# Minimal_carrier_board_for_CM4_rev_C.net
KiCad netlist of a schematic drawn in EAGLE
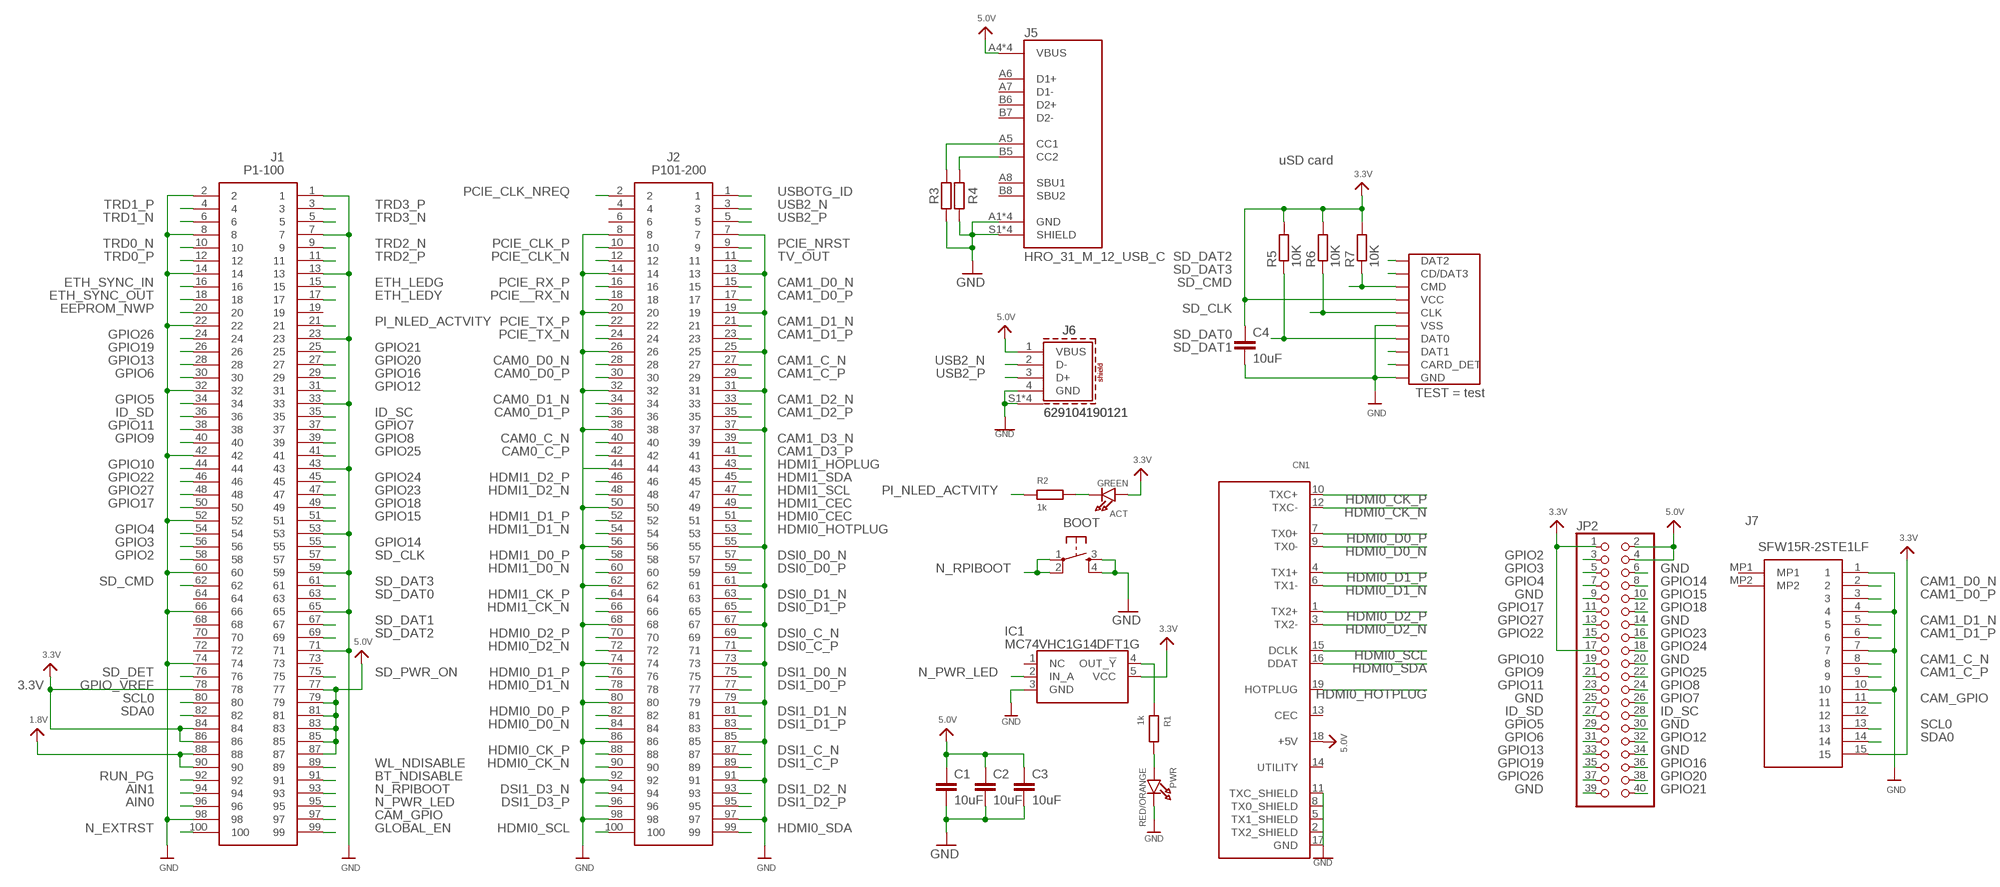
[diagram p0: schematic, sheet 1]

(export (version "E")
  (design (tool "Eeschema 10.0.6"))
  (components
    (comp (ref "ACT")
      (value "GREEN")
      (footprint "eagle-import:CHIPLED_0805_NOOUTLINE")
      (libsource (lib "eagle-import") (part "LED0805_NOOUTLINE"))
    )
    (comp (ref "BOOT")
      (value "TACTILE_SWITCHE_5X5_MICRO_")
      (footprint "eagle-import:TACTILE_SWITCH_5X5_MICRO")
      (libsource (lib "eagle-import") (part "TACTILE_SWITCHE_5X5_MICRO_"))
    )
    (comp (ref "C1")
      (value "10uF")
      (footprint "eagle-import:C0805")
      (libsource (lib "eagle-import") (part "C-EUC0805"))
    )
    (comp (ref "C2")
      (value "10uF")
      (footprint "eagle-import:C0805")
      (libsource (lib "eagle-import") (part "C-EUC0805"))
    )
    (comp (ref "C3")
      (value "10uF")
      (footprint "eagle-import:C0805")
      (libsource (lib "eagle-import") (part "C-EUC0805"))
    )
    (comp (ref "C4")
      (value "10uF")
      (footprint "eagle-import:C0805")
      (libsource (lib "eagle-import") (part "C-EUC0805"))
    )
    (comp (ref "CN1")
      (value "HDMI_MOLEX_47151-0001")
      (footprint "eagle-import:HDMI_MOLEX_47151-0001")
      (libsource (lib "eagle-import") (part "HDMI_MOLEX_47151-0001"))
    )
    (comp (ref "IC1")
      (value "MC74VHC1G14DFT1G")
      (footprint "eagle-import:SOT65P210X110-5N")
      (fields (field (name "MOUSER_PART_NUMBER") "863-MC74VHC1G14DFT1G"))
      (libsource (lib "eagle-import") (part "MC74VHC1G14DFT1G"))
    )
    (comp (ref "J1")
      (value "P1-100")
      (footprint "eagle-import:DF40C100DS04V51")
      (fields
        (field (name "MANUFACTURER_PART_NUMBER") "DF40C-100DS-0.4V(51)")
        (field (name "MOUSER_PART_NUMBER") "798-DF40C100DS0.4V51")
      )
      (libsource (lib "eagle-import") (part "DF40C-100DS-0.4V_51_"))
    )
    (comp (ref "J2")
      (value "P101-200")
      (footprint "eagle-import:DF40C100DS04V51")
      (fields
        (field (name "MANUFACTURER_PART_NUMBER") "DF40C-100DS-0.4V(51)")
        (field (name "MOUSER_PART_NUMBER") "798-DF40C100DS0.4V51")
      )
      (libsource (lib "eagle-import") (part "DF40C-100DS-0.4V_51_"))
    )
    (comp (ref "J5")
      (value "HRO_31_M_12_USB_C")
      (footprint "eagle-import:HRO_31_M_12_USB_C")
      (libsource (lib "eagle-import") (part "HRO_31_M_12_USB_C"))
    )
    (comp (ref "J6")
      (value "629104190121")
      (footprint "eagle-import:629104190121")
      (libsource (lib "eagle-import") (part "629104190121"))
    )
    (comp (ref "J7")
      (value "SFW15R-2STE1LF")
      (footprint "eagle-import:SFW15R2STE1LF")
      (fields (field (name "MOUSER_PART_NUMBER") "649-SFW15R-2STE1LF"))
      (libsource (lib "eagle-import") (part "SFW15R-2STE1LF"))
    )
    (comp (ref "JP2")
      (value "PINHD-2X20")
      (footprint "eagle-import:2X20")
      (libsource (lib "eagle-import") (part "PINHD-2X20"))
    )
    (comp (ref "PWR")
      (value "RED/ORANGE")
      (footprint "eagle-import:CHIPLED_0805_NOOUTLINE")
      (libsource (lib "eagle-import") (part "LED0805_NOOUTLINE"))
    )
    (comp (ref "R1")
      (value "1k")
      (footprint "eagle-import:R0805")
      (libsource (lib "eagle-import") (part "R-EU_R0805"))
    )
    (comp (ref "R2")
      (value "1k")
      (footprint "eagle-import:R0805")
      (libsource (lib "eagle-import") (part "R-EU_R0805"))
    )
    (comp (ref "R3")
      (value "5.1k")
      (footprint "eagle-import:R0805")
      (libsource (lib "eagle-import") (part "R-EU_R0805"))
    )
    (comp (ref "R4")
      (value "5.1k")
      (footprint "eagle-import:R0805")
      (libsource (lib "eagle-import") (part "R-EU_R0805"))
    )
    (comp (ref "R5")
      (value "10K")
      (footprint "eagle-import:R0805")
      (libsource (lib "eagle-import") (part "R-EU_R0805"))
    )
    (comp (ref "R6")
      (value "10K")
      (footprint "eagle-import:R0805")
      (libsource (lib "eagle-import") (part "R-EU_R0805"))
    )
    (comp (ref "R7")
      (value "10K")
      (footprint "eagle-import:R0805")
      (libsource (lib "eagle-import") (part "R-EU_R0805"))
    )
    (comp (ref "SD_CARD")
      (value "MICRO_SD_CARD_")
      (footprint "eagle-import:TFP09-2--12B")
      (fields (field (name "TEST") "test"))
      (libsource (lib "eagle-import") (part "MICRO_SD_CARD_"))
    )
  )
  (nets
    (net (code "1") (name "/AIN0") (class "Default")
      (node (ref "J1") (pin "96") (pinfunction "96_96") (pintype "bidirectional"))
    )
    (net (code "2") (name "/AIN1") (class "Default")
      (node (ref "J1") (pin "94") (pinfunction "94_94") (pintype "bidirectional"))
    )
    (net (code "3") (name "/BT_NDISABLE") (class "Default")
      (node (ref "J1") (pin "91") (pinfunction "91_91") (pintype "bidirectional"))
    )
    (net (code "4") (name "/CAM0_C_N") (class "Default")
      (node (ref "J2") (pin "40") (pinfunction "40_40") (pintype "bidirectional"))
    )
    (net (code "5") (name "/CAM0_C_P") (class "Default")
      (node (ref "J2") (pin "42") (pinfunction "42_42") (pintype "bidirectional"))
    )
    (net (code "6") (name "/CAM0_D0_N") (class "Default")
      (node (ref "J2") (pin "28") (pinfunction "28_28") (pintype "bidirectional"))
    )
    (net (code "7") (name "/CAM0_D0_P") (class "Default")
      (node (ref "J2") (pin "30") (pinfunction "30_30") (pintype "bidirectional"))
    )
    (net (code "8") (name "/CAM0_D1_N") (class "Default")
      (node (ref "J2") (pin "34") (pinfunction "34_34") (pintype "bidirectional"))
    )
    (net (code "9") (name "/CAM0_D1_P") (class "Default")
      (node (ref "J2") (pin "36") (pinfunction "36_36") (pintype "bidirectional"))
    )
    (net (code "10") (name "/CAM1_C_N") (class "Default")
      (node (ref "J2") (pin "27") (pinfunction "27_27") (pintype "bidirectional"))
      (node (ref "J7") (pin "8") (pinfunction "8_8") (pintype "bidirectional"))
    )
    (net (code "11") (name "/CAM1_C_P") (class "Default")
      (node (ref "J2") (pin "29") (pinfunction "29_29") (pintype "bidirectional"))
      (node (ref "J7") (pin "9") (pinfunction "9_9") (pintype "bidirectional"))
    )
    (net (code "12") (name "/CAM1_D0_N") (class "Default")
      (node (ref "J2") (pin "15") (pinfunction "15_15") (pintype "bidirectional"))
      (node (ref "J7") (pin "2") (pinfunction "2_2") (pintype "bidirectional"))
    )
    (net (code "13") (name "/CAM1_D0_P") (class "Default")
      (node (ref "J2") (pin "17") (pinfunction "17_17") (pintype "bidirectional"))
      (node (ref "J7") (pin "3") (pinfunction "3_3") (pintype "bidirectional"))
    )
    (net (code "14") (name "/CAM1_D1_N") (class "Default")
      (node (ref "J2") (pin "21") (pinfunction "21_21") (pintype "bidirectional"))
      (node (ref "J7") (pin "5") (pinfunction "5_5") (pintype "bidirectional"))
    )
    (net (code "15") (name "/CAM1_D1_P") (class "Default")
      (node (ref "J2") (pin "23") (pinfunction "23_23") (pintype "bidirectional"))
      (node (ref "J7") (pin "6") (pinfunction "6_6") (pintype "bidirectional"))
    )
    (net (code "16") (name "/CAM1_D2_N") (class "Default")
      (node (ref "J2") (pin "33") (pinfunction "33_33") (pintype "bidirectional"))
    )
    (net (code "17") (name "/CAM1_D2_P") (class "Default")
      (node (ref "J2") (pin "35") (pinfunction "35_35") (pintype "bidirectional"))
    )
    (net (code "18") (name "/CAM1_D3_N") (class "Default")
      (node (ref "J2") (pin "39") (pinfunction "39_39") (pintype "bidirectional"))
    )
    (net (code "19") (name "/CAM1_D3_P") (class "Default")
      (node (ref "J2") (pin "41") (pinfunction "41_41") (pintype "bidirectional"))
    )
    (net (code "20") (name "/CAM_GPIO") (class "Default")
      (node (ref "J1") (pin "97") (pinfunction "97_97") (pintype "bidirectional"))
      (node (ref "J7") (pin "11") (pinfunction "11_11") (pintype "bidirectional"))
    )
    (net (code "21") (name "/DSI0_C_N") (class "Default")
      (node (ref "J2") (pin "69") (pinfunction "69_69") (pintype "bidirectional"))
    )
    (net (code "22") (name "/DSI0_C_P") (class "Default")
      (node (ref "J2") (pin "71") (pinfunction "71_71") (pintype "bidirectional"))
    )
    (net (code "23") (name "/DSI0_D0_N") (class "Default")
      (node (ref "J2") (pin "57") (pinfunction "57_57") (pintype "bidirectional"))
    )
    (net (code "24") (name "/DSI0_D0_P") (class "Default")
      (node (ref "J2") (pin "59") (pinfunction "59_59") (pintype "bidirectional"))
    )
    (net (code "25") (name "/DSI0_D1_N") (class "Default")
      (node (ref "J2") (pin "63") (pinfunction "63_63") (pintype "bidirectional"))
    )
    (net (code "26") (name "/DSI0_D1_P") (class "Default")
      (node (ref "J2") (pin "65") (pinfunction "65_65") (pintype "bidirectional"))
    )
    (net (code "27") (name "/DSI1_C_N") (class "Default")
      (node (ref "J2") (pin "87") (pinfunction "87_87") (pintype "bidirectional"))
    )
    (net (code "28") (name "/DSI1_C_P") (class "Default")
      (node (ref "J2") (pin "89") (pinfunction "89_89") (pintype "bidirectional"))
    )
    (net (code "29") (name "/DSI1_D0_N") (class "Default")
      (node (ref "J2") (pin "75") (pinfunction "75_75") (pintype "bidirectional"))
    )
    (net (code "30") (name "/DSI1_D0_P") (class "Default")
      (node (ref "J2") (pin "77") (pinfunction "77_77") (pintype "bidirectional"))
    )
    (net (code "31") (name "/DSI1_D1_N") (class "Default")
      (node (ref "J2") (pin "81") (pinfunction "81_81") (pintype "bidirectional"))
    )
    (net (code "32") (name "/DSI1_D1_P") (class "Default")
      (node (ref "J2") (pin "83") (pinfunction "83_83") (pintype "bidirectional"))
    )
    (net (code "33") (name "/DSI1_D2_N") (class "Default")
      (node (ref "J2") (pin "93") (pinfunction "93_93") (pintype "bidirectional"))
    )
    (net (code "34") (name "/DSI1_D2_P") (class "Default")
      (node (ref "J2") (pin "95") (pinfunction "95_95") (pintype "bidirectional"))
    )
    (net (code "35") (name "/DSI1_D3_N") (class "Default")
      (node (ref "J2") (pin "94") (pinfunction "94_94") (pintype "bidirectional"))
    )
    (net (code "36") (name "/DSI1_D3_P") (class "Default")
      (node (ref "J2") (pin "96") (pinfunction "96_96") (pintype "bidirectional"))
    )
    (net (code "37") (name "/EEPROM_NWP") (class "Default")
      (node (ref "J1") (pin "20") (pinfunction "20_20") (pintype "bidirectional"))
    )
    (net (code "38") (name "/ETH_LEDG") (class "Default")
      (node (ref "J1") (pin "15") (pinfunction "15_15") (pintype "bidirectional"))
    )
    (net (code "39") (name "/ETH_LEDY") (class "Default")
      (node (ref "J1") (pin "17") (pinfunction "17_17") (pintype "bidirectional"))
    )
    (net (code "40") (name "/ETH_SYNC_IN") (class "Default")
      (node (ref "J1") (pin "16") (pinfunction "16_16") (pintype "bidirectional"))
    )
    (net (code "41") (name "/ETH_SYNC_OUT") (class "Default")
      (node (ref "J1") (pin "18") (pinfunction "18_18") (pintype "bidirectional"))
    )
    (net (code "42") (name "/GLOBAL_EN") (class "Default")
      (node (ref "J1") (pin "99") (pinfunction "99_99") (pintype "bidirectional"))
    )
    (net (code "43") (name "/GPIO2") (class "Default")
      (node (ref "J1") (pin "58") (pinfunction "58_58") (pintype "bidirectional"))
      (node (ref "JP2") (pin "3") (pinfunction "3_3") (pintype "passive"))
    )
    (net (code "44") (name "/GPIO3") (class "Default")
      (node (ref "J1") (pin "56") (pinfunction "56_56") (pintype "bidirectional"))
      (node (ref "JP2") (pin "5") (pinfunction "5_5") (pintype "passive"))
    )
    (net (code "45") (name "/GPIO4") (class "Default")
      (node (ref "J1") (pin "54") (pinfunction "54_54") (pintype "bidirectional"))
      (node (ref "JP2") (pin "7") (pinfunction "7_7") (pintype "passive"))
    )
    (net (code "46") (name "/GPIO5") (class "Default")
      (node (ref "J1") (pin "34") (pinfunction "34_34") (pintype "bidirectional"))
      (node (ref "JP2") (pin "29") (pinfunction "29_29") (pintype "passive"))
    )
    (net (code "47") (name "/GPIO6") (class "Default")
      (node (ref "J1") (pin "30") (pinfunction "30_30") (pintype "bidirectional"))
      (node (ref "JP2") (pin "31") (pinfunction "31_31") (pintype "passive"))
    )
    (net (code "48") (name "/GPIO7") (class "Default")
      (node (ref "J1") (pin "37") (pinfunction "37_37") (pintype "bidirectional"))
      (node (ref "JP2") (pin "26") (pinfunction "26_26") (pintype "passive"))
    )
    (net (code "49") (name "/GPIO8") (class "Default")
      (node (ref "J1") (pin "39") (pinfunction "39_39") (pintype "bidirectional"))
      (node (ref "JP2") (pin "24") (pinfunction "24_24") (pintype "passive"))
    )
    (net (code "50") (name "/GPIO9") (class "Default")
      (node (ref "J1") (pin "40") (pinfunction "40_40") (pintype "bidirectional"))
      (node (ref "JP2") (pin "21") (pinfunction "21_21") (pintype "passive"))
    )
    (net (code "51") (name "/GPIO10") (class "Default")
      (node (ref "J1") (pin "44") (pinfunction "44_44") (pintype "bidirectional"))
      (node (ref "JP2") (pin "19") (pinfunction "19_19") (pintype "passive"))
    )
    (net (code "52") (name "/GPIO11") (class "Default")
      (node (ref "J1") (pin "38") (pinfunction "38_38") (pintype "bidirectional"))
      (node (ref "JP2") (pin "23") (pinfunction "23_23") (pintype "passive"))
    )
    (net (code "53") (name "/GPIO12") (class "Default")
      (node (ref "J1") (pin "31") (pinfunction "31_31") (pintype "bidirectional"))
      (node (ref "JP2") (pin "32") (pinfunction "32_32") (pintype "passive"))
    )
    (net (code "54") (name "/GPIO13") (class "Default")
      (node (ref "J1") (pin "28") (pinfunction "28_28") (pintype "bidirectional"))
      (node (ref "JP2") (pin "33") (pinfunction "33_33") (pintype "passive"))
    )
    (net (code "55") (name "/GPIO14") (class "Default")
      (node (ref "J1") (pin "55") (pinfunction "55_55") (pintype "bidirectional"))
      (node (ref "JP2") (pin "8") (pinfunction "8_8") (pintype "passive"))
    )
    (net (code "56") (name "/GPIO15") (class "Default")
      (node (ref "J1") (pin "51") (pinfunction "51_51") (pintype "bidirectional"))
      (node (ref "JP2") (pin "10") (pinfunction "10_10") (pintype "passive"))
    )
    (net (code "57") (name "/GPIO16") (class "Default")
      (node (ref "J1") (pin "29") (pinfunction "29_29") (pintype "bidirectional"))
      (node (ref "JP2") (pin "36") (pinfunction "36_36") (pintype "passive"))
    )
    (net (code "58") (name "/GPIO17") (class "Default")
      (node (ref "J1") (pin "50") (pinfunction "50_50") (pintype "bidirectional"))
      (node (ref "JP2") (pin "11") (pinfunction "11_11") (pintype "passive"))
    )
    (net (code "59") (name "/GPIO18") (class "Default")
      (node (ref "J1") (pin "49") (pinfunction "49_49") (pintype "bidirectional"))
      (node (ref "JP2") (pin "12") (pinfunction "12_12") (pintype "passive"))
    )
    (net (code "60") (name "/GPIO19") (class "Default")
      (node (ref "J1") (pin "26") (pinfunction "26_26") (pintype "bidirectional"))
      (node (ref "JP2") (pin "35") (pinfunction "35_35") (pintype "passive"))
    )
    (net (code "61") (name "/GPIO20") (class "Default")
      (node (ref "J1") (pin "27") (pinfunction "27_27") (pintype "bidirectional"))
      (node (ref "JP2") (pin "38") (pinfunction "38_38") (pintype "passive"))
    )
    (net (code "62") (name "/GPIO21") (class "Default")
      (node (ref "J1") (pin "25") (pinfunction "25_25") (pintype "bidirectional"))
      (node (ref "JP2") (pin "40") (pinfunction "40_40") (pintype "passive"))
    )
    (net (code "63") (name "/GPIO22") (class "Default")
      (node (ref "J1") (pin "46") (pinfunction "46_46") (pintype "bidirectional"))
      (node (ref "JP2") (pin "15") (pinfunction "15_15") (pintype "passive"))
    )
    (net (code "64") (name "/GPIO23") (class "Default")
      (node (ref "J1") (pin "47") (pinfunction "47_47") (pintype "bidirectional"))
      (node (ref "JP2") (pin "16") (pinfunction "16_16") (pintype "passive"))
    )
    (net (code "65") (name "/GPIO24") (class "Default")
      (node (ref "J1") (pin "45") (pinfunction "45_45") (pintype "bidirectional"))
      (node (ref "JP2") (pin "18") (pinfunction "18_18") (pintype "passive"))
    )
    (net (code "66") (name "/GPIO25") (class "Default")
      (node (ref "J1") (pin "41") (pinfunction "41_41") (pintype "bidirectional"))
      (node (ref "JP2") (pin "22") (pinfunction "22_22") (pintype "passive"))
    )
    (net (code "67") (name "/GPIO26") (class "Default")
      (node (ref "J1") (pin "24") (pinfunction "24_24") (pintype "bidirectional"))
      (node (ref "JP2") (pin "37") (pinfunction "37_37") (pintype "passive"))
    )
    (net (code "68") (name "/GPIO27") (class "Default")
      (node (ref "J1") (pin "48") (pinfunction "48_48") (pintype "bidirectional"))
      (node (ref "JP2") (pin "13") (pinfunction "13_13") (pintype "passive"))
    )
    (net (code "69") (name "/HDMI0_CEC") (class "Default")
      (node (ref "J2") (pin "51") (pinfunction "51_51") (pintype "bidirectional"))
    )
    (net (code "70") (name "/HDMI0_CK_N") (class "Default")
      (node (ref "CN1") (pin "12") (pinfunction "TXC-_12") (pintype "bidirectional"))
      (node (ref "J2") (pin "90") (pinfunction "90_90") (pintype "bidirectional"))
    )
    (net (code "71") (name "/HDMI0_CK_P") (class "Default")
      (node (ref "CN1") (pin "10") (pinfunction "TXC+_10") (pintype "bidirectional"))
      (node (ref "J2") (pin "88") (pinfunction "88_88") (pintype "bidirectional"))
    )
    (net (code "72") (name "/HDMI0_D0_N") (class "Default")
      (node (ref "CN1") (pin "9") (pinfunction "TX0-_9") (pintype "bidirectional"))
      (node (ref "J2") (pin "84") (pinfunction "84_84") (pintype "bidirectional"))
    )
    (net (code "73") (name "/HDMI0_D0_P") (class "Default")
      (node (ref "CN1") (pin "7") (pinfunction "TX0+_7") (pintype "bidirectional"))
      (node (ref "J2") (pin "82") (pinfunction "82_82") (pintype "bidirectional"))
    )
    (net (code "74") (name "/HDMI0_D1_N") (class "Default")
      (node (ref "CN1") (pin "6") (pinfunction "TX1-_6") (pintype "bidirectional"))
      (node (ref "J2") (pin "78") (pinfunction "78_78") (pintype "bidirectional"))
    )
    (net (code "75") (name "/HDMI0_D1_P") (class "Default")
      (node (ref "CN1") (pin "4") (pinfunction "TX1+_4") (pintype "bidirectional"))
      (node (ref "J2") (pin "76") (pinfunction "76_76") (pintype "bidirectional"))
    )
    (net (code "76") (name "/HDMI0_D2_N") (class "Default")
      (node (ref "CN1") (pin "3") (pinfunction "TX2-_3") (pintype "bidirectional"))
      (node (ref "J2") (pin "72") (pinfunction "72_72") (pintype "bidirectional"))
    )
    (net (code "77") (name "/HDMI0_D2_P") (class "Default")
      (node (ref "CN1") (pin "1") (pinfunction "TX2+_1") (pintype "bidirectional"))
      (node (ref "J2") (pin "70") (pinfunction "70_70") (pintype "bidirectional"))
    )
    (net (code "78") (name "/HDMI0_HOTPLUG") (class "Default")
      (node (ref "CN1") (pin "19") (pinfunction "HOTPLUG_19") (pintype "bidirectional"))
      (node (ref "J2") (pin "53") (pinfunction "53_53") (pintype "bidirectional"))
    )
    (net (code "79") (name "/HDMI0_SCL") (class "Default")
      (node (ref "CN1") (pin "15") (pinfunction "DCLK_15") (pintype "bidirectional"))
      (node (ref "J2") (pin "100") (pinfunction "100_100") (pintype "bidirectional"))
    )
    (net (code "80") (name "/HDMI0_SDA") (class "Default")
      (node (ref "CN1") (pin "16") (pinfunction "DDAT_16") (pintype "bidirectional"))
      (node (ref "J2") (pin "99") (pinfunction "99_99") (pintype "bidirectional"))
    )
    (net (code "81") (name "/HDMI1_CEC") (class "Default")
      (node (ref "J2") (pin "49") (pinfunction "49_49") (pintype "bidirectional"))
    )
    (net (code "82") (name "/HDMI1_CK_N") (class "Default")
      (node (ref "J2") (pin "66") (pinfunction "66_66") (pintype "bidirectional"))
    )
    (net (code "83") (name "/HDMI1_CK_P") (class "Default")
      (node (ref "J2") (pin "64") (pinfunction "64_64") (pintype "bidirectional"))
    )
    (net (code "84") (name "/HDMI1_D0_N") (class "Default")
      (node (ref "J2") (pin "60") (pinfunction "60_60") (pintype "bidirectional"))
    )
    (net (code "85") (name "/HDMI1_D0_P") (class "Default")
      (node (ref "J2") (pin "58") (pinfunction "58_58") (pintype "bidirectional"))
    )
    (net (code "86") (name "/HDMI1_D1_N") (class "Default")
      (node (ref "J2") (pin "54") (pinfunction "54_54") (pintype "bidirectional"))
    )
    (net (code "87") (name "/HDMI1_D1_P") (class "Default")
      (node (ref "J2") (pin "52") (pinfunction "52_52") (pintype "bidirectional"))
    )
    (net (code "88") (name "/HDMI1_D2_N") (class "Default")
      (node (ref "J2") (pin "48") (pinfunction "48_48") (pintype "bidirectional"))
    )
    (net (code "89") (name "/HDMI1_D2_P") (class "Default")
      (node (ref "J2") (pin "46") (pinfunction "46_46") (pintype "bidirectional"))
    )
    (net (code "90") (name "/HDMI1_HOPLUG") (class "Default")
      (node (ref "J2") (pin "43") (pinfunction "43_43") (pintype "bidirectional"))
    )
    (net (code "91") (name "/HDMI1_SCL") (class "Default")
      (node (ref "J2") (pin "47") (pinfunction "47_47") (pintype "bidirectional"))
    )
    (net (code "92") (name "/HDMI1_SDA") (class "Default")
      (node (ref "J2") (pin "45") (pinfunction "45_45") (pintype "bidirectional"))
    )
    (net (code "93") (name "/ID_SC") (class "Default")
      (node (ref "J1") (pin "35") (pinfunction "35_35") (pintype "bidirectional"))
      (node (ref "JP2") (pin "28") (pinfunction "28_28") (pintype "passive"))
    )
    (net (code "94") (name "/ID_SD") (class "Default")
      (node (ref "J1") (pin "36") (pinfunction "36_36") (pintype "bidirectional"))
      (node (ref "JP2") (pin "27") (pinfunction "27_27") (pintype "passive"))
    )
    (net (code "95") (name "/N_EXTRST") (class "Default")
      (node (ref "J1") (pin "100") (pinfunction "100_100") (pintype "bidirectional"))
    )
    (net (code "96") (name "/N_PWR_LED") (class "Default")
      (node (ref "IC1") (pin "2") (pinfunction "IN_A_2") (pintype "input"))
      (node (ref "J1") (pin "95") (pinfunction "95_95") (pintype "bidirectional"))
    )
    (net (code "97") (name "/N_RPIBOOT") (class "Default")
      (node (ref "BOOT") (pin "1") (pinfunction "1_1") (pintype "passive"))
      (node (ref "BOOT") (pin "2") (pinfunction "2_2") (pintype "passive"))
      (node (ref "J1") (pin "93") (pinfunction "93_93") (pintype "bidirectional"))
    )
    (net (code "98") (name "/PCIE_CLK_N") (class "Default")
      (node (ref "J2") (pin "12") (pinfunction "12_12") (pintype "bidirectional"))
    )
    (net (code "99") (name "/PCIE_CLK_NREQ") (class "Default")
      (node (ref "J2") (pin "2") (pinfunction "2_2") (pintype "bidirectional"))
    )
    (net (code "100") (name "/PCIE_CLK_P") (class "Default")
      (node (ref "J2") (pin "10") (pinfunction "10_10") (pintype "bidirectional"))
    )
    (net (code "101") (name "/PCIE_NRST") (class "Default")
      (node (ref "J2") (pin "9") (pinfunction "9_9") (pintype "bidirectional"))
    )
    (net (code "102") (name "/PCIE_RX_P") (class "Default")
      (node (ref "J2") (pin "16") (pinfunction "16_16") (pintype "bidirectional"))
    )
    (net (code "103") (name "/PCIE_TX_N") (class "Default")
      (node (ref "J2") (pin "24") (pinfunction "24_24") (pintype "bidirectional"))
    )
    (net (code "104") (name "/PCIE_TX_P") (class "Default")
      (node (ref "J2") (pin "22") (pinfunction "22_22") (pintype "bidirectional"))
    )
    (net (code "105") (name "/PCIE__RX_N") (class "Default")
      (node (ref "J2") (pin "18") (pinfunction "18_18") (pintype "bidirectional"))
    )
    (net (code "106") (name "/PI_NLED_ACTVITY") (class "Default")
      (node (ref "J1") (pin "21") (pinfunction "21_21") (pintype "bidirectional"))
      (node (ref "R2") (pin "1") (pinfunction "1_1") (pintype "passive"))
    )
    (net (code "107") (name "/RUN_PG") (class "Default")
      (node (ref "J1") (pin "92") (pinfunction "92_92") (pintype "bidirectional"))
    )
    (net (code "108") (name "/SCL0") (class "Default")
      (node (ref "J1") (pin "80") (pinfunction "80_80") (pintype "bidirectional"))
      (node (ref "J7") (pin "13") (pinfunction "13_13") (pintype "bidirectional"))
    )
    (net (code "109") (name "/SDA0") (class "Default")
      (node (ref "J1") (pin "82") (pinfunction "82_82") (pintype "bidirectional"))
      (node (ref "J7") (pin "14") (pinfunction "14_14") (pintype "bidirectional"))
    )
    (net (code "110") (name "/SD_CLK") (class "Default")
      (node (ref "J1") (pin "57") (pinfunction "57_57") (pintype "bidirectional"))
      (node (ref "R6") (pin "1") (pinfunction "1_1") (pintype "passive"))
      (node (ref "SD_CARD") (pin "CLK") (pinfunction "CLK_CLK") (pintype "bidirectional"))
    )
    (net (code "111") (name "/SD_CMD") (class "Default")
      (node (ref "J1") (pin "62") (pinfunction "62_62") (pintype "bidirectional"))
      (node (ref "R7") (pin "1") (pinfunction "1_1") (pintype "passive"))
      (node (ref "SD_CARD") (pin "CMD") (pinfunction "CMD_CMD") (pintype "bidirectional"))
    )
    (net (code "112") (name "/SD_DAT0") (class "Default")
      (node (ref "J1") (pin "63") (pinfunction "63_63") (pintype "bidirectional"))
      (node (ref "R5") (pin "1") (pinfunction "1_1") (pintype "passive"))
      (node (ref "SD_CARD") (pin "DAT0") (pinfunction "DAT0_DAT0") (pintype "bidirectional"))
    )
    (net (code "113") (name "/SD_DAT1") (class "Default")
      (node (ref "J1") (pin "67") (pinfunction "67_67") (pintype "bidirectional"))
      (node (ref "SD_CARD") (pin "DAT1") (pinfunction "DAT1_DAT1") (pintype "bidirectional"))
    )
    (net (code "114") (name "/SD_DAT2") (class "Default")
      (node (ref "J1") (pin "69") (pinfunction "69_69") (pintype "bidirectional"))
      (node (ref "SD_CARD") (pin "DAT2") (pinfunction "DAT2_DAT2") (pintype "bidirectional"))
    )
    (net (code "115") (name "/SD_DAT3") (class "Default")
      (node (ref "J1") (pin "61") (pinfunction "61_61") (pintype "bidirectional"))
      (node (ref "SD_CARD") (pin "CD/DAT3") (pinfunction "CD/DAT3_CD/DAT3") (pintype "bidirectional"))
    )
    (net (code "116") (name "/SD_DET") (class "Default")
      (node (ref "J1") (pin "76") (pinfunction "76_76") (pintype "bidirectional"))
    )
    (net (code "117") (name "/SD_PWR_ON") (class "Default")
      (node (ref "J1") (pin "75") (pinfunction "75_75") (pintype "bidirectional"))
    )
    (net (code "118") (name "/TRD0_N") (class "Default")
      (node (ref "J1") (pin "10") (pinfunction "10_10") (pintype "bidirectional"))
    )
    (net (code "119") (name "/TRD0_P") (class "Default")
      (node (ref "J1") (pin "12") (pinfunction "12_12") (pintype "bidirectional"))
    )
    (net (code "120") (name "/TRD1_N") (class "Default")
      (node (ref "J1") (pin "6") (pinfunction "6_6") (pintype "bidirectional"))
    )
    (net (code "121") (name "/TRD1_P") (class "Default")
      (node (ref "J1") (pin "4") (pinfunction "4_4") (pintype "bidirectional"))
    )
    (net (code "122") (name "/TRD2_N") (class "Default")
      (node (ref "J1") (pin "9") (pinfunction "9_9") (pintype "bidirectional"))
    )
    (net (code "123") (name "/TRD2_P") (class "Default")
      (node (ref "J1") (pin "11") (pinfunction "11_11") (pintype "bidirectional"))
    )
    (net (code "124") (name "/TRD3_N") (class "Default")
      (node (ref "J1") (pin "5") (pinfunction "5_5") (pintype "bidirectional"))
    )
    (net (code "125") (name "/TRD3_P") (class "Default")
      (node (ref "J1") (pin "3") (pinfunction "3_3") (pintype "bidirectional"))
    )
    (net (code "126") (name "/TV_OUT") (class "Default")
      (node (ref "J2") (pin "11") (pinfunction "11_11") (pintype "bidirectional"))
    )
    (net (code "127") (name "/USB2_N") (class "Default")
      (node (ref "J2") (pin "3") (pinfunction "3_3") (pintype "bidirectional"))
      (node (ref "J6") (pin "2") (pinfunction "D-_2") (pintype "bidirectional"))
    )
    (net (code "128") (name "/USB2_P") (class "Default")
      (node (ref "J2") (pin "5") (pinfunction "5_5") (pintype "bidirectional"))
      (node (ref "J6") (pin "3") (pinfunction "D+_3") (pintype "bidirectional"))
    )
    (net (code "129") (name "/USBOTG_ID") (class "Default")
      (node (ref "J2") (pin "1") (pinfunction "1_1") (pintype "bidirectional"))
    )
    (net (code "130") (name "/WL_NDISABLE") (class "Default")
      (node (ref "J1") (pin "89") (pinfunction "89_89") (pintype "bidirectional"))
    )
    (net (code "131") (name "1.8V") (class "Default")
      (node (ref "J1") (pin "88") (pinfunction "88_88") (pintype "bidirectional"))
      (node (ref "J1") (pin "90") (pinfunction "90_90") (pintype "bidirectional"))
    )
    (net (code "132") (name "3.3V") (class "Default")
      (node (ref "ACT") (pin "A") (pinfunction "A_A") (pintype "passive"))
      (node (ref "C4") (pin "1") (pinfunction "1_1") (pintype "passive"))
      (node (ref "IC1") (pin "5") (pinfunction "VCC_5") (pintype "power_in"))
      (node (ref "J1") (pin "78") (pinfunction "78_78") (pintype "bidirectional"))
      (node (ref "J1") (pin "84") (pinfunction "84_84") (pintype "bidirectional"))
      (node (ref "J1") (pin "86") (pinfunction "86_86") (pintype "bidirectional"))
      (node (ref "J7") (pin "15") (pinfunction "15_15") (pintype "bidirectional"))
      (node (ref "JP2") (pin "1") (pinfunction "1_1") (pintype "passive"))
      (node (ref "JP2") (pin "17") (pinfunction "17_17") (pintype "passive"))
      (node (ref "R5") (pin "2") (pinfunction "2_2") (pintype "passive"))
      (node (ref "R6") (pin "2") (pinfunction "2_2") (pintype "passive"))
      (node (ref "R7") (pin "2") (pinfunction "2_2") (pintype "passive"))
      (node (ref "SD_CARD") (pin "VCC") (pinfunction "VCC_VCC") (pintype "bidirectional"))
    )
    (net (code "133") (name "5.0V") (class "Default")
      (node (ref "C1") (pin "1") (pinfunction "1_1") (pintype "passive"))
      (node (ref "C2") (pin "1") (pinfunction "1_1") (pintype "passive"))
      (node (ref "C3") (pin "1") (pinfunction "1_1") (pintype "passive"))
      (node (ref "CN1") (pin "18") (pinfunction "+5V_18") (pintype "power_in"))
      (node (ref "J1") (pin "77") (pinfunction "77_77") (pintype "bidirectional"))
      (node (ref "J1") (pin "79") (pinfunction "79_79") (pintype "bidirectional"))
      (node (ref "J1") (pin "81") (pinfunction "81_81") (pintype "bidirectional"))
      (node (ref "J1") (pin "83") (pinfunction "83_83") (pintype "bidirectional"))
      (node (ref "J1") (pin "85") (pinfunction "85_85") (pintype "bidirectional"))
      (node (ref "J1") (pin "87") (pinfunction "87_87") (pintype "bidirectional"))
      (node (ref "J5") (pin "A4") (pinfunction "VBUS_A4") (pintype "passive"))
      (node (ref "J5") (pin "A9") (pinfunction "VBUS_A9") (pintype "passive"))
      (node (ref "J5") (pin "B4") (pinfunction "VBUS_B4") (pintype "passive"))
      (node (ref "J5") (pin "B9") (pinfunction "VBUS_B9") (pintype "passive"))
      (node (ref "J6") (pin "1") (pinfunction "VBUS_1") (pintype "bidirectional"))
      (node (ref "JP2") (pin "2") (pinfunction "2_2") (pintype "passive"))
      (node (ref "JP2") (pin "4") (pinfunction "4_4") (pintype "passive"))
    )
    (net (code "134") (name "GND") (class "Default")
      (node (ref "BOOT") (pin "3") (pinfunction "3_3") (pintype "passive"))
      (node (ref "BOOT") (pin "4") (pinfunction "4_4") (pintype "passive"))
      (node (ref "C1") (pin "2") (pinfunction "2_2") (pintype "passive"))
      (node (ref "C2") (pin "2") (pinfunction "2_2") (pintype "passive"))
      (node (ref "C3") (pin "2") (pinfunction "2_2") (pintype "passive"))
      (node (ref "C4") (pin "2") (pinfunction "2_2") (pintype "passive"))
      (node (ref "CN1") (pin "11") (pinfunction "TXC_SHIELD_11") (pintype "power_in"))
      (node (ref "CN1") (pin "17") (pinfunction "GND_17") (pintype "power_in"))
      (node (ref "CN1") (pin "2") (pinfunction "TX2_SHIELD_2") (pintype "power_in"))
      (node (ref "CN1") (pin "5") (pinfunction "TX1_SHIELD_5") (pintype "power_in"))
      (node (ref "CN1") (pin "8") (pinfunction "TX0_SHIELD_8") (pintype "power_in"))
      (node (ref "IC1") (pin "3") (pinfunction "GND_3") (pintype "power_in"))
      (node (ref "J1") (pin "1") (pinfunction "1_1") (pintype "bidirectional"))
      (node (ref "J1") (pin "13") (pinfunction "13_13") (pintype "bidirectional"))
      (node (ref "J1") (pin "14") (pinfunction "14_14") (pintype "bidirectional"))
      (node (ref "J1") (pin "2") (pinfunction "2_2") (pintype "bidirectional"))
      (node (ref "J1") (pin "22") (pinfunction "22_22") (pintype "bidirectional"))
      (node (ref "J1") (pin "23") (pinfunction "23_23") (pintype "bidirectional"))
      (node (ref "J1") (pin "32") (pinfunction "32_32") (pintype "bidirectional"))
      (node (ref "J1") (pin "33") (pinfunction "33_33") (pintype "bidirectional"))
      (node (ref "J1") (pin "42") (pinfunction "42_42") (pintype "bidirectional"))
      (node (ref "J1") (pin "43") (pinfunction "43_43") (pintype "bidirectional"))
      (node (ref "J1") (pin "52") (pinfunction "52_52") (pintype "bidirectional"))
      (node (ref "J1") (pin "53") (pinfunction "53_53") (pintype "bidirectional"))
      (node (ref "J1") (pin "59") (pinfunction "59_59") (pintype "bidirectional"))
      (node (ref "J1") (pin "60") (pinfunction "60_60") (pintype "bidirectional"))
      (node (ref "J1") (pin "65") (pinfunction "65_65") (pintype "bidirectional"))
      (node (ref "J1") (pin "66") (pinfunction "66_66") (pintype "bidirectional"))
      (node (ref "J1") (pin "7") (pinfunction "7_7") (pintype "bidirectional"))
      (node (ref "J1") (pin "71") (pinfunction "71_71") (pintype "bidirectional"))
      (node (ref "J1") (pin "74") (pinfunction "74_74") (pintype "bidirectional"))
      (node (ref "J1") (pin "8") (pinfunction "8_8") (pintype "bidirectional"))
      (node (ref "J1") (pin "98") (pinfunction "98_98") (pintype "bidirectional"))
      (node (ref "J2") (pin "13") (pinfunction "13_13") (pintype "bidirectional"))
      (node (ref "J2") (pin "14") (pinfunction "14_14") (pintype "bidirectional"))
      (node (ref "J2") (pin "19") (pinfunction "19_19") (pintype "bidirectional"))
      (node (ref "J2") (pin "20") (pinfunction "20_20") (pintype "bidirectional"))
      (node (ref "J2") (pin "25") (pinfunction "25_25") (pintype "bidirectional"))
      (node (ref "J2") (pin "26") (pinfunction "26_26") (pintype "bidirectional"))
      (node (ref "J2") (pin "31") (pinfunction "31_31") (pintype "bidirectional"))
      (node (ref "J2") (pin "32") (pinfunction "32_32") (pintype "bidirectional"))
      (node (ref "J2") (pin "37") (pinfunction "37_37") (pintype "bidirectional"))
      (node (ref "J2") (pin "38") (pinfunction "38_38") (pintype "bidirectional"))
      (node (ref "J2") (pin "44") (pinfunction "44_44") (pintype "bidirectional"))
      (node (ref "J2") (pin "50") (pinfunction "50_50") (pintype "bidirectional"))
      (node (ref "J2") (pin "55") (pinfunction "55_55") (pintype "bidirectional"))
      (node (ref "J2") (pin "56") (pinfunction "56_56") (pintype "bidirectional"))
      (node (ref "J2") (pin "61") (pinfunction "61_61") (pintype "bidirectional"))
      (node (ref "J2") (pin "62") (pinfunction "62_62") (pintype "bidirectional"))
      (node (ref "J2") (pin "67") (pinfunction "67_67") (pintype "bidirectional"))
      (node (ref "J2") (pin "68") (pinfunction "68_68") (pintype "bidirectional"))
      (node (ref "J2") (pin "7") (pinfunction "7_7") (pintype "bidirectional"))
      (node (ref "J2") (pin "73") (pinfunction "73_73") (pintype "bidirectional"))
      (node (ref "J2") (pin "74") (pinfunction "74_74") (pintype "bidirectional"))
      (node (ref "J2") (pin "79") (pinfunction "79_79") (pintype "bidirectional"))
      (node (ref "J2") (pin "8") (pinfunction "8_8") (pintype "bidirectional"))
      (node (ref "J2") (pin "80") (pinfunction "80_80") (pintype "bidirectional"))
      (node (ref "J2") (pin "85") (pinfunction "85_85") (pintype "bidirectional"))
      (node (ref "J2") (pin "86") (pinfunction "86_86") (pintype "bidirectional"))
      (node (ref "J2") (pin "91") (pinfunction "91_91") (pintype "bidirectional"))
      (node (ref "J2") (pin "92") (pinfunction "92_92") (pintype "bidirectional"))
      (node (ref "J2") (pin "97") (pinfunction "97_97") (pintype "bidirectional"))
      (node (ref "J2") (pin "98") (pinfunction "98_98") (pintype "bidirectional"))
      (node (ref "J5") (pin "A1") (pinfunction "GND_A1") (pintype "passive"))
      (node (ref "J5") (pin "A12") (pinfunction "GND_A12") (pintype "passive"))
      (node (ref "J5") (pin "B1") (pinfunction "GND_B1") (pintype "passive"))
      (node (ref "J5") (pin "B12") (pinfunction "GND_B12") (pintype "passive"))
      (node (ref "J5") (pin "S1") (pinfunction "SHIELD_S1") (pintype "passive"))
      (node (ref "J5") (pin "S2") (pinfunction "SHIELD_S2") (pintype "passive"))
      (node (ref "J5") (pin "S3") (pinfunction "SHIELD_S3") (pintype "passive"))
      (node (ref "J5") (pin "S4") (pinfunction "SHIELD_S4") (pintype "passive"))
      (node (ref "J6") (pin "4") (pinfunction "GND_4") (pintype "bidirectional"))
      (node (ref "J6") (pin "S1") (pinfunction "SHIELD_S1") (pintype "bidirectional"))
      (node (ref "J6") (pin "S2") (pinfunction "SHIELD_S2") (pintype "bidirectional"))
      (node (ref "J6") (pin "S3") (pinfunction "SHIELD_S3") (pintype "bidirectional"))
      (node (ref "J6") (pin "S4") (pinfunction "SHIELD_S4") (pintype "bidirectional"))
      (node (ref "J7") (pin "1") (pinfunction "1_1") (pintype "bidirectional"))
      (node (ref "J7") (pin "10") (pinfunction "10_10") (pintype "bidirectional"))
      (node (ref "J7") (pin "4") (pinfunction "4_4") (pintype "bidirectional"))
      (node (ref "J7") (pin "7") (pinfunction "7_7") (pintype "bidirectional"))
      (node (ref "JP2") (pin "14") (pinfunction "14_14") (pintype "passive"))
      (node (ref "JP2") (pin "20") (pinfunction "20_20") (pintype "passive"))
      (node (ref "JP2") (pin "25") (pinfunction "25_25") (pintype "passive"))
      (node (ref "JP2") (pin "30") (pinfunction "30_30") (pintype "passive"))
      (node (ref "JP2") (pin "34") (pinfunction "34_34") (pintype "passive"))
      (node (ref "JP2") (pin "39") (pinfunction "39_39") (pintype "passive"))
      (node (ref "JP2") (pin "6") (pinfunction "6_6") (pintype "passive"))
      (node (ref "JP2") (pin "9") (pinfunction "9_9") (pintype "passive"))
      (node (ref "PWR") (pin "C") (pinfunction "C_C") (pintype "passive"))
      (node (ref "R3") (pin "1") (pinfunction "1_1") (pintype "passive"))
      (node (ref "R4") (pin "2") (pinfunction "2_2") (pintype "passive"))
      (node (ref "SD_CARD") (pin "GND") (pinfunction "GND_GND") (pintype "bidirectional"))
      (node (ref "SD_CARD") (pin "GND@1") (pinfunction "GND_GND@1") (pintype "bidirectional"))
      (node (ref "SD_CARD") (pin "GND@2") (pinfunction "GND_GND@2") (pintype "bidirectional"))
      (node (ref "SD_CARD") (pin "GND@3") (pinfunction "VSS_GND@3") (pintype "bidirectional"))
      (node (ref "SD_CARD") (pin "VSS") (pinfunction "GND_VSS") (pintype "bidirectional"))
    )
    (net (code "135") (name "Net-(ACT-PadC)") (class "Default")
      (node (ref "ACT") (pin "C") (pinfunction "C_C") (pintype "passive"))
      (node (ref "R2") (pin "2") (pinfunction "2_2") (pintype "passive"))
    )
    (net (code "136") (name "Net-(IC1-OUT_~{Y})") (class "Default")
      (node (ref "IC1") (pin "4") (pinfunction "OUT_~{Y}_4") (pintype "output"))
      (node (ref "R1") (pin "1") (pinfunction "1_1") (pintype "passive"))
    )
    (net (code "137") (name "Net-(J5-CC1)") (class "Default")
      (node (ref "J5") (pin "A5") (pinfunction "CC1_A5") (pintype "passive"))
      (node (ref "R3") (pin "2") (pinfunction "2_2") (pintype "passive"))
    )
    (net (code "138") (name "Net-(J5-CC2)") (class "Default")
      (node (ref "J5") (pin "B5") (pinfunction "CC2_B5") (pintype "passive"))
      (node (ref "R4") (pin "1") (pinfunction "1_1") (pintype "passive"))
    )
    (net (code "139") (name "Net-(PWR-PadA)") (class "Default")
      (node (ref "PWR") (pin "A") (pinfunction "A_A") (pintype "passive"))
      (node (ref "R1") (pin "2") (pinfunction "2_2") (pintype "passive"))
    )
    (net (code "140") (name "unconnected-(CN1A-CEC-Pad13)") (class "Default")
      (node (ref "CN1") (pin "13") (pinfunction "CEC_13") (pintype "bidirectional"))
    )
    (net (code "141") (name "unconnected-(CN1A-UTILITY-Pad14)") (class "Default")
      (node (ref "CN1") (pin "14") (pinfunction "UTILITY_14") (pintype "bidirectional"))
    )
    (net (code "142") (name "unconnected-(IC1-NC-Pad1)") (class "Default")
      (node (ref "IC1") (pin "1") (pinfunction "NC_1") (pintype "no_connect"))
    )
    (net (code "143") (name "unconnected-(J1-Pad19)") (class "Default")
      (node (ref "J1") (pin "19") (pinfunction "19_19") (pintype "bidirectional"))
    )
    (net (code "144") (name "unconnected-(J1-Pad64)") (class "Default")
      (node (ref "J1") (pin "64") (pinfunction "64_64") (pintype "bidirectional"))
    )
    (net (code "145") (name "unconnected-(J1-Pad68)") (class "Default")
      (node (ref "J1") (pin "68") (pinfunction "68_68") (pintype "bidirectional"))
    )
    (net (code "146") (name "unconnected-(J1-Pad70)") (class "Default")
      (node (ref "J1") (pin "70") (pinfunction "70_70") (pintype "bidirectional"))
    )
    (net (code "147") (name "unconnected-(J1-Pad72)") (class "Default")
      (node (ref "J1") (pin "72") (pinfunction "72_72") (pintype "bidirectional"))
    )
    (net (code "148") (name "unconnected-(J1-Pad73)") (class "Default")
      (node (ref "J1") (pin "73") (pinfunction "73_73") (pintype "bidirectional"))
    )
    (net (code "149") (name "unconnected-(J2-Pad4)") (class "Default")
      (node (ref "J2") (pin "4") (pinfunction "4_4") (pintype "bidirectional"))
    )
    (net (code "150") (name "unconnected-(J2-Pad6)") (class "Default")
      (node (ref "J2") (pin "6") (pinfunction "6_6") (pintype "bidirectional"))
    )
    (net (code "151") (name "unconnected-(J5-D1+-PadA6)") (class "Default")
      (node (ref "J5") (pin "A6") (pinfunction "D1+_A6") (pintype "passive"))
    )
    (net (code "152") (name "unconnected-(J5-D1--PadA7)") (class "Default")
      (node (ref "J5") (pin "A7") (pinfunction "D1-_A7") (pintype "passive"))
    )
    (net (code "153") (name "unconnected-(J5-D2+-PadB6)") (class "Default")
      (node (ref "J5") (pin "B6") (pinfunction "D2+_B6") (pintype "passive"))
    )
    (net (code "154") (name "unconnected-(J5-D2--PadB7)") (class "Default")
      (node (ref "J5") (pin "B7") (pinfunction "D2-_B7") (pintype "passive"))
    )
    (net (code "155") (name "unconnected-(J5-SBU1-PadA8)") (class "Default")
      (node (ref "J5") (pin "A8") (pinfunction "SBU1_A8") (pintype "passive"))
    )
    (net (code "156") (name "unconnected-(J5-SBU2-PadB8)") (class "Default")
      (node (ref "J5") (pin "B8") (pinfunction "SBU2_B8") (pintype "passive"))
    )
    (net (code "157") (name "unconnected-(J7-Pad12)") (class "Default")
      (node (ref "J7") (pin "12") (pinfunction "12_12") (pintype "bidirectional"))
    )
    (net (code "158") (name "unconnected-(J7-PadMP1)") (class "Default")
      (node (ref "J7") (pin "MP1") (pinfunction "MP1_MP1") (pintype "bidirectional"))
    )
    (net (code "159") (name "unconnected-(J7-PadMP2)") (class "Default")
      (node (ref "J7") (pin "MP2") (pinfunction "MP2_MP2") (pintype "bidirectional"))
    )
    (net (code "160") (name "unconnected-(SD_CARD-CARD_DET-PadCD)") (class "Default")
      (node (ref "SD_CARD") (pin "CD") (pinfunction "CARD_DET_CD") (pintype "bidirectional"))
    )
  )
)
